# rapidshark-butt-break-mk-2_0.net
KiCad netlist of a schematic drawn in EAGLE
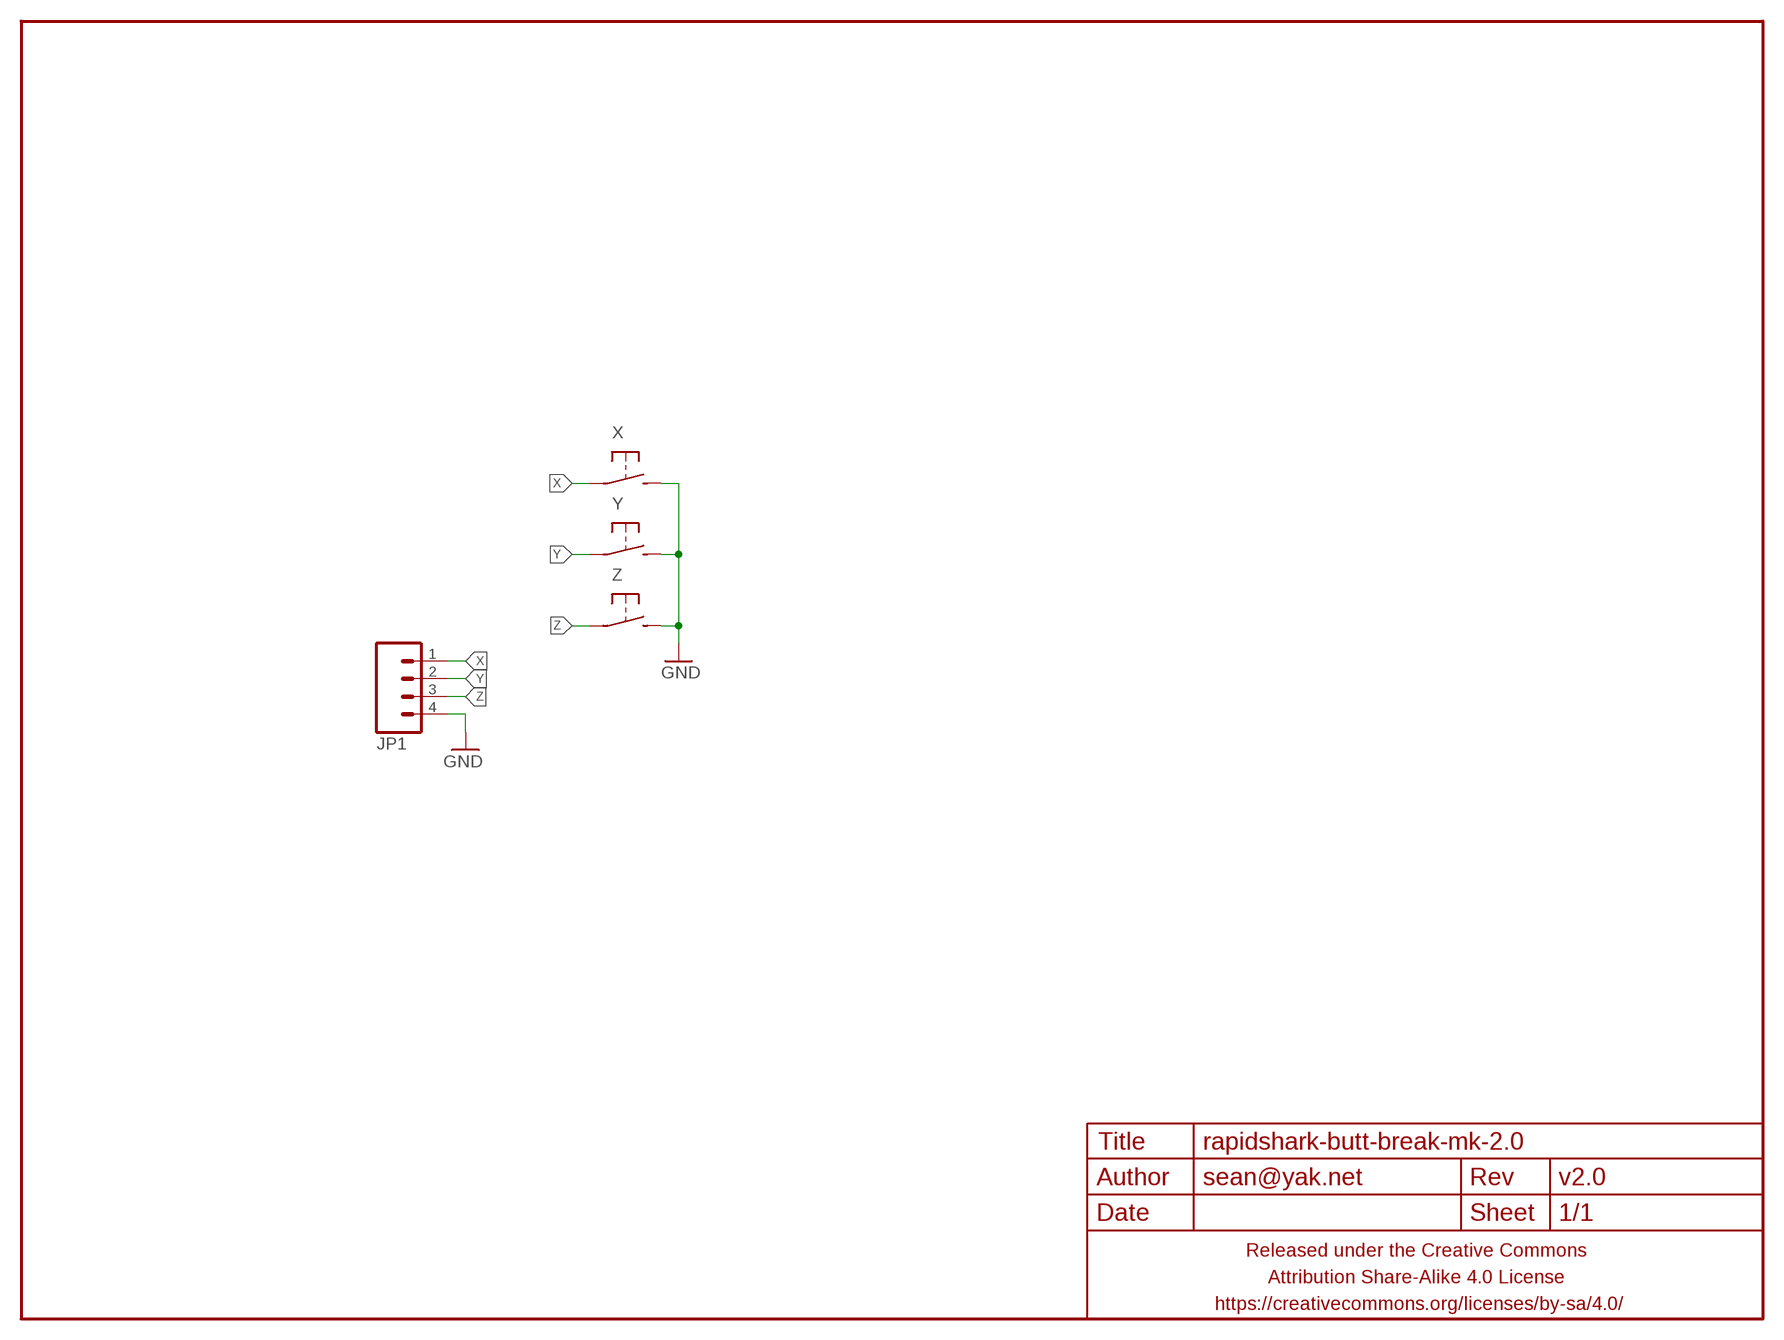
[diagram p0: schematic, sheet 1]

(export (version "E")
  (design (tool "Eeschema 10.0.6"))
  (components
    (comp (ref "FRAME1")
      (value "FRAME-LETTERNO_PACKAGE")
      (footprint "eagle-import:DUMMY")
      (fields (field (name "DESIGNER") "sean@yak.net") (field (name "VERSION") "v2.0"))
      (libsource (lib "eagle-import") (part "FRAME-LETTERNO_PACKAGE"))
    )
    (comp (ref "JP1")
      (value "M04JST-PTH")
      (footprint "eagle-import:JST-4-PH-RA-PTH")
      (libsource (lib "eagle-import") (part "M04JST-PTH"))
    )
    (comp (ref "X")
      (value "SPST-NO-TACT3MM-PTH-SMALL-PADS")
      (footprint "eagle-import:DTS-3-SMALL-PADS")
      (libsource (lib "eagle-import") (part "SPST-NO-TACT3MM-PTH-SMALL-PADS"))
    )
    (comp (ref "Y")
      (value "SPST-NO-TACT3MM-PTH-SMALL-PADS")
      (footprint "eagle-import:DTS-3-SMALL-PADS")
      (libsource (lib "eagle-import") (part "SPST-NO-TACT3MM-PTH-SMALL-PADS"))
    )
    (comp (ref "Z")
      (value "SPST-NO-TACT3MM-PTH-SMALL-PADS")
      (footprint "eagle-import:DTS-3-SMALL-PADS")
      (libsource (lib "eagle-import") (part "SPST-NO-TACT3MM-PTH-SMALL-PADS"))
    )
  )
  (nets
    (net (code "1") (name "GND") (class "Default")
      (node (ref "JP1") (pin "4") (pinfunction "4_4") (pintype "passive"))
      (node (ref "X") (pin "2") (pinfunction "2_2") (pintype "passive"))
      (node (ref "Y") (pin "2") (pinfunction "2_2") (pintype "passive"))
      (node (ref "Z") (pin "2") (pinfunction "2_2") (pintype "passive"))
    )
    (net (code "2") (name "X") (class "Default")
      (node (ref "JP1") (pin "1") (pinfunction "1_1") (pintype "passive"))
      (node (ref "X") (pin "1") (pinfunction "1_1") (pintype "passive"))
    )
    (net (code "3") (name "Y") (class "Default")
      (node (ref "JP1") (pin "2") (pinfunction "2_2") (pintype "passive"))
      (node (ref "Y") (pin "1") (pinfunction "1_1") (pintype "passive"))
    )
    (net (code "4") (name "Z") (class "Default")
      (node (ref "JP1") (pin "3") (pinfunction "3_3") (pintype "passive"))
      (node (ref "Z") (pin "1") (pinfunction "1_1") (pintype "passive"))
    )
  )
)
